# microcondsk.net
KiCad netlist of a schematic drawn in EAGLE
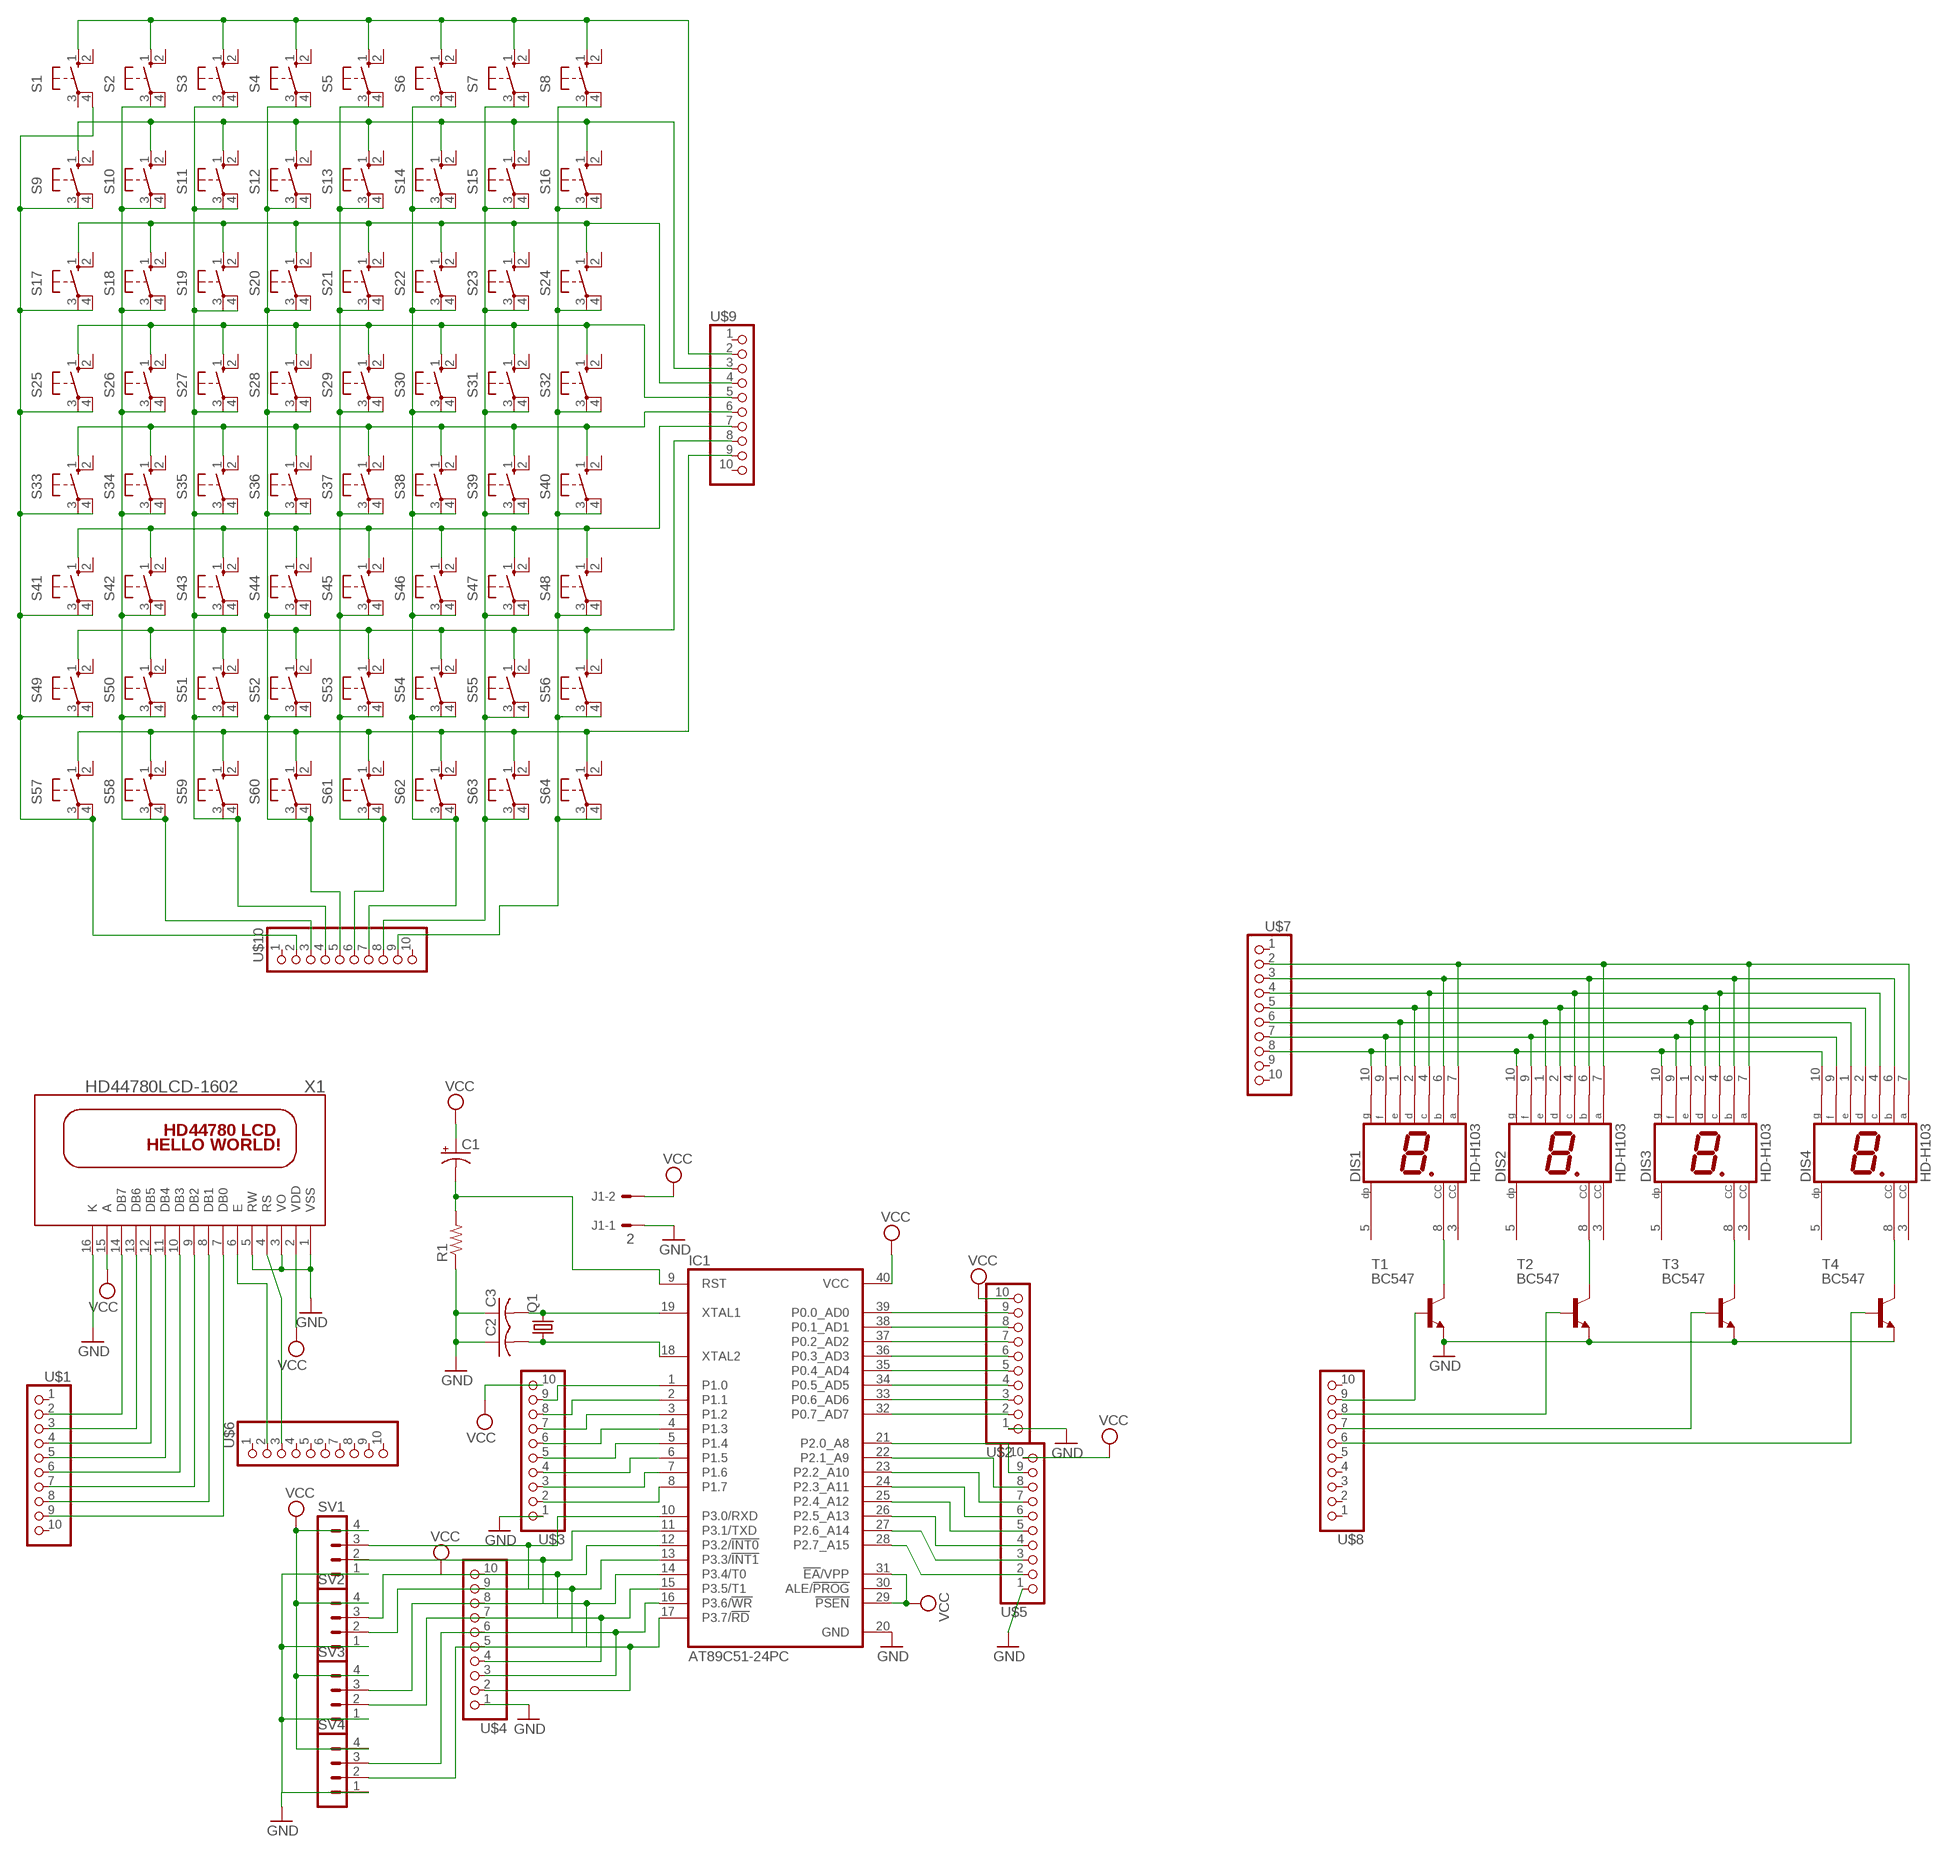
[diagram p0: schematic, sheet 1]

(export (version "E")
  (design (tool "Eeschema 10.0.6"))
  (components
    (comp (ref "C1")
      (value "CPOL-USE2-5")
      (footprint "eagle-import:E2-5")
      (libsource (lib "eagle-import") (part "CPOL-USE2-5"))
    )
    (comp (ref "C2")
      (value "C-US025-025X050")
      (footprint "eagle-import:C025-025X050")
      (libsource (lib "eagle-import") (part "C-US025-025X050"))
    )
    (comp (ref "C3")
      (value "C-US025-025X050")
      (footprint "eagle-import:C025-025X050")
      (libsource (lib "eagle-import") (part "C-US025-025X050"))
    )
    (comp (ref "DIS1")
      (value "HD-H103")
      (footprint "eagle-import:HDSP-M")
      (libsource (lib "eagle-import") (part "HD-H103"))
    )
    (comp (ref "DIS2")
      (value "HD-H103")
      (footprint "eagle-import:HDSP-M")
      (libsource (lib "eagle-import") (part "HD-H103"))
    )
    (comp (ref "DIS3")
      (value "HD-H103")
      (footprint "eagle-import:HDSP-M")
      (libsource (lib "eagle-import") (part "HD-H103"))
    )
    (comp (ref "DIS4")
      (value "HD-H103")
      (footprint "eagle-import:HDSP-M")
      (libsource (lib "eagle-import") (part "HD-H103"))
    )
    (comp (ref "IC1")
      (value "AT89C51-24PC")
      (footprint "eagle-import:DIL40")
      (libsource (lib "eagle-import") (part "AT89C51-PC24"))
    )
    (comp (ref "J1")
      (value "2")
      (footprint "eagle-import:6410-02")
      (libsource (lib "eagle-import") (part "22-?-0227-2021"))
    )
    (comp (ref "Q1")
      (value "CRYSTALHC49U-V")
      (footprint "eagle-import:HC49U-V")
      (libsource (lib "eagle-import") (part "CRYSTALHC49U-V"))
    )
    (comp (ref "R1")
      (value "R-US_0204/7")
      (footprint "eagle-import:0204_7")
      (libsource (lib "eagle-import") (part "R-US_0204/7"))
    )
    (comp (ref "S1")
      (value "10-XX")
      (footprint "eagle-import:B3F-10XX")
      (fields (field (name "MPN") "B3F-1000"))
      (libsource (lib "eagle-import") (part "10-XX"))
    )
    (comp (ref "S2")
      (value "10-XX")
      (footprint "eagle-import:B3F-10XX")
      (fields (field (name "MPN") "B3F-1000"))
      (libsource (lib "eagle-import") (part "10-XX"))
    )
    (comp (ref "S3")
      (value "10-XX")
      (footprint "eagle-import:B3F-10XX")
      (fields (field (name "MPN") "B3F-1000"))
      (libsource (lib "eagle-import") (part "10-XX"))
    )
    (comp (ref "S4")
      (value "10-XX")
      (footprint "eagle-import:B3F-10XX")
      (fields (field (name "MPN") "B3F-1000"))
      (libsource (lib "eagle-import") (part "10-XX"))
    )
    (comp (ref "S5")
      (value "10-XX")
      (footprint "eagle-import:B3F-10XX")
      (fields (field (name "MPN") "B3F-1000"))
      (libsource (lib "eagle-import") (part "10-XX"))
    )
    (comp (ref "S6")
      (value "10-XX")
      (footprint "eagle-import:B3F-10XX")
      (fields (field (name "MPN") "B3F-1000"))
      (libsource (lib "eagle-import") (part "10-XX"))
    )
    (comp (ref "S7")
      (value "10-XX")
      (footprint "eagle-import:B3F-10XX")
      (fields (field (name "MPN") "B3F-1000"))
      (libsource (lib "eagle-import") (part "10-XX"))
    )
    (comp (ref "S8")
      (value "10-XX")
      (footprint "eagle-import:B3F-10XX")
      (fields (field (name "MPN") "B3F-1000"))
      (libsource (lib "eagle-import") (part "10-XX"))
    )
    (comp (ref "S9")
      (value "10-XX")
      (footprint "eagle-import:B3F-10XX")
      (fields (field (name "MPN") "B3F-1000"))
      (libsource (lib "eagle-import") (part "10-XX"))
    )
    (comp (ref "S10")
      (value "10-XX")
      (footprint "eagle-import:B3F-10XX")
      (fields (field (name "MPN") "B3F-1000"))
      (libsource (lib "eagle-import") (part "10-XX"))
    )
    (comp (ref "S11")
      (value "10-XX")
      (footprint "eagle-import:B3F-10XX")
      (fields (field (name "MPN") "B3F-1000"))
      (libsource (lib "eagle-import") (part "10-XX"))
    )
    (comp (ref "S12")
      (value "10-XX")
      (footprint "eagle-import:B3F-10XX")
      (fields (field (name "MPN") "B3F-1000"))
      (libsource (lib "eagle-import") (part "10-XX"))
    )
    (comp (ref "S13")
      (value "10-XX")
      (footprint "eagle-import:B3F-10XX")
      (fields (field (name "MPN") "B3F-1000"))
      (libsource (lib "eagle-import") (part "10-XX"))
    )
    (comp (ref "S14")
      (value "10-XX")
      (footprint "eagle-import:B3F-10XX")
      (fields (field (name "MPN") "B3F-1000"))
      (libsource (lib "eagle-import") (part "10-XX"))
    )
    (comp (ref "S15")
      (value "10-XX")
      (footprint "eagle-import:B3F-10XX")
      (fields (field (name "MPN") "B3F-1000"))
      (libsource (lib "eagle-import") (part "10-XX"))
    )
    (comp (ref "S16")
      (value "10-XX")
      (footprint "eagle-import:B3F-10XX")
      (fields (field (name "MPN") "B3F-1000"))
      (libsource (lib "eagle-import") (part "10-XX"))
    )
    (comp (ref "S17")
      (value "10-XX")
      (footprint "eagle-import:B3F-10XX")
      (fields (field (name "MPN") "B3F-1000"))
      (libsource (lib "eagle-import") (part "10-XX"))
    )
    (comp (ref "S18")
      (value "10-XX")
      (footprint "eagle-import:B3F-10XX")
      (fields (field (name "MPN") "B3F-1000"))
      (libsource (lib "eagle-import") (part "10-XX"))
    )
    (comp (ref "S19")
      (value "10-XX")
      (footprint "eagle-import:B3F-10XX")
      (fields (field (name "MPN") "B3F-1000"))
      (libsource (lib "eagle-import") (part "10-XX"))
    )
    (comp (ref "S20")
      (value "10-XX")
      (footprint "eagle-import:B3F-10XX")
      (fields (field (name "MPN") "B3F-1000"))
      (libsource (lib "eagle-import") (part "10-XX"))
    )
    (comp (ref "S21")
      (value "10-XX")
      (footprint "eagle-import:B3F-10XX")
      (fields (field (name "MPN") "B3F-1000"))
      (libsource (lib "eagle-import") (part "10-XX"))
    )
    (comp (ref "S22")
      (value "10-XX")
      (footprint "eagle-import:B3F-10XX")
      (fields (field (name "MPN") "B3F-1000"))
      (libsource (lib "eagle-import") (part "10-XX"))
    )
    (comp (ref "S23")
      (value "10-XX")
      (footprint "eagle-import:B3F-10XX")
      (fields (field (name "MPN") "B3F-1000"))
      (libsource (lib "eagle-import") (part "10-XX"))
    )
    (comp (ref "S24")
      (value "10-XX")
      (footprint "eagle-import:B3F-10XX")
      (fields (field (name "MPN") "B3F-1000"))
      (libsource (lib "eagle-import") (part "10-XX"))
    )
    (comp (ref "S25")
      (value "10-XX")
      (footprint "eagle-import:B3F-10XX")
      (fields (field (name "MPN") "B3F-1000"))
      (libsource (lib "eagle-import") (part "10-XX"))
    )
    (comp (ref "S26")
      (value "10-XX")
      (footprint "eagle-import:B3F-10XX")
      (fields (field (name "MPN") "B3F-1000"))
      (libsource (lib "eagle-import") (part "10-XX"))
    )
    (comp (ref "S27")
      (value "10-XX")
      (footprint "eagle-import:B3F-10XX")
      (fields (field (name "MPN") "B3F-1000"))
      (libsource (lib "eagle-import") (part "10-XX"))
    )
    (comp (ref "S28")
      (value "10-XX")
      (footprint "eagle-import:B3F-10XX")
      (fields (field (name "MPN") "B3F-1000"))
      (libsource (lib "eagle-import") (part "10-XX"))
    )
    (comp (ref "S29")
      (value "10-XX")
      (footprint "eagle-import:B3F-10XX")
      (fields (field (name "MPN") "B3F-1000"))
      (libsource (lib "eagle-import") (part "10-XX"))
    )
    (comp (ref "S30")
      (value "10-XX")
      (footprint "eagle-import:B3F-10XX")
      (fields (field (name "MPN") "B3F-1000"))
      (libsource (lib "eagle-import") (part "10-XX"))
    )
    (comp (ref "S31")
      (value "10-XX")
      (footprint "eagle-import:B3F-10XX")
      (fields (field (name "MPN") "B3F-1000"))
      (libsource (lib "eagle-import") (part "10-XX"))
    )
    (comp (ref "S32")
      (value "10-XX")
      (footprint "eagle-import:B3F-10XX")
      (fields (field (name "MPN") "B3F-1000"))
      (libsource (lib "eagle-import") (part "10-XX"))
    )
    (comp (ref "S33")
      (value "10-XX")
      (footprint "eagle-import:B3F-10XX")
      (fields (field (name "MPN") "B3F-1000"))
      (libsource (lib "eagle-import") (part "10-XX"))
    )
    (comp (ref "S34")
      (value "10-XX")
      (footprint "eagle-import:B3F-10XX")
      (fields (field (name "MPN") "B3F-1000"))
      (libsource (lib "eagle-import") (part "10-XX"))
    )
    (comp (ref "S35")
      (value "10-XX")
      (footprint "eagle-import:B3F-10XX")
      (fields (field (name "MPN") "B3F-1000"))
      (libsource (lib "eagle-import") (part "10-XX"))
    )
    (comp (ref "S36")
      (value "10-XX")
      (footprint "eagle-import:B3F-10XX")
      (fields (field (name "MPN") "B3F-1000"))
      (libsource (lib "eagle-import") (part "10-XX"))
    )
    (comp (ref "S37")
      (value "10-XX")
      (footprint "eagle-import:B3F-10XX")
      (fields (field (name "MPN") "B3F-1000"))
      (libsource (lib "eagle-import") (part "10-XX"))
    )
    (comp (ref "S38")
      (value "10-XX")
      (footprint "eagle-import:B3F-10XX")
      (fields (field (name "MPN") "B3F-1000"))
      (libsource (lib "eagle-import") (part "10-XX"))
    )
    (comp (ref "S39")
      (value "10-XX")
      (footprint "eagle-import:B3F-10XX")
      (fields (field (name "MPN") "B3F-1000"))
      (libsource (lib "eagle-import") (part "10-XX"))
    )
    (comp (ref "S40")
      (value "10-XX")
      (footprint "eagle-import:B3F-10XX")
      (fields (field (name "MPN") "B3F-1000"))
      (libsource (lib "eagle-import") (part "10-XX"))
    )
    (comp (ref "S41")
      (value "10-XX")
      (footprint "eagle-import:B3F-10XX")
      (fields (field (name "MPN") "B3F-1000"))
      (libsource (lib "eagle-import") (part "10-XX"))
    )
    (comp (ref "S42")
      (value "10-XX")
      (footprint "eagle-import:B3F-10XX")
      (fields (field (name "MPN") "B3F-1000"))
      (libsource (lib "eagle-import") (part "10-XX"))
    )
    (comp (ref "S43")
      (value "10-XX")
      (footprint "eagle-import:B3F-10XX")
      (fields (field (name "MPN") "B3F-1000"))
      (libsource (lib "eagle-import") (part "10-XX"))
    )
    (comp (ref "S44")
      (value "10-XX")
      (footprint "eagle-import:B3F-10XX")
      (fields (field (name "MPN") "B3F-1000"))
      (libsource (lib "eagle-import") (part "10-XX"))
    )
    (comp (ref "S45")
      (value "10-XX")
      (footprint "eagle-import:B3F-10XX")
      (fields (field (name "MPN") "B3F-1000"))
      (libsource (lib "eagle-import") (part "10-XX"))
    )
    (comp (ref "S46")
      (value "10-XX")
      (footprint "eagle-import:B3F-10XX")
      (fields (field (name "MPN") "B3F-1000"))
      (libsource (lib "eagle-import") (part "10-XX"))
    )
    (comp (ref "S47")
      (value "10-XX")
      (footprint "eagle-import:B3F-10XX")
      (fields (field (name "MPN") "B3F-1000"))
      (libsource (lib "eagle-import") (part "10-XX"))
    )
    (comp (ref "S48")
      (value "10-XX")
      (footprint "eagle-import:B3F-10XX")
      (fields (field (name "MPN") "B3F-1000"))
      (libsource (lib "eagle-import") (part "10-XX"))
    )
    (comp (ref "S49")
      (value "10-XX")
      (footprint "eagle-import:B3F-10XX")
      (fields (field (name "MPN") "B3F-1000"))
      (libsource (lib "eagle-import") (part "10-XX"))
    )
    (comp (ref "S50")
      (value "10-XX")
      (footprint "eagle-import:B3F-10XX")
      (fields (field (name "MPN") "B3F-1000"))
      (libsource (lib "eagle-import") (part "10-XX"))
    )
    (comp (ref "S51")
      (value "10-XX")
      (footprint "eagle-import:B3F-10XX")
      (fields (field (name "MPN") "B3F-1000"))
      (libsource (lib "eagle-import") (part "10-XX"))
    )
    (comp (ref "S52")
      (value "10-XX")
      (footprint "eagle-import:B3F-10XX")
      (fields (field (name "MPN") "B3F-1000"))
      (libsource (lib "eagle-import") (part "10-XX"))
    )
    (comp (ref "S53")
      (value "10-XX")
      (footprint "eagle-import:B3F-10XX")
      (fields (field (name "MPN") "B3F-1000"))
      (libsource (lib "eagle-import") (part "10-XX"))
    )
    (comp (ref "S54")
      (value "10-XX")
      (footprint "eagle-import:B3F-10XX")
      (fields (field (name "MPN") "B3F-1000"))
      (libsource (lib "eagle-import") (part "10-XX"))
    )
    (comp (ref "S55")
      (value "10-XX")
      (footprint "eagle-import:B3F-10XX")
      (fields (field (name "MPN") "B3F-1000"))
      (libsource (lib "eagle-import") (part "10-XX"))
    )
    (comp (ref "S56")
      (value "10-XX")
      (footprint "eagle-import:B3F-10XX")
      (fields (field (name "MPN") "B3F-1000"))
      (libsource (lib "eagle-import") (part "10-XX"))
    )
    (comp (ref "S57")
      (value "10-XX")
      (footprint "eagle-import:B3F-10XX")
      (fields (field (name "MPN") "B3F-1000"))
      (libsource (lib "eagle-import") (part "10-XX"))
    )
    (comp (ref "S58")
      (value "10-XX")
      (footprint "eagle-import:B3F-10XX")
      (fields (field (name "MPN") "B3F-1000"))
      (libsource (lib "eagle-import") (part "10-XX"))
    )
    (comp (ref "S59")
      (value "10-XX")
      (footprint "eagle-import:B3F-10XX")
      (fields (field (name "MPN") "B3F-1000"))
      (libsource (lib "eagle-import") (part "10-XX"))
    )
    (comp (ref "S60")
      (value "10-XX")
      (footprint "eagle-import:B3F-10XX")
      (fields (field (name "MPN") "B3F-1000"))
      (libsource (lib "eagle-import") (part "10-XX"))
    )
    (comp (ref "S61")
      (value "10-XX")
      (footprint "eagle-import:B3F-10XX")
      (fields (field (name "MPN") "B3F-1000"))
      (libsource (lib "eagle-import") (part "10-XX"))
    )
    (comp (ref "S62")
      (value "10-XX")
      (footprint "eagle-import:B3F-10XX")
      (fields (field (name "MPN") "B3F-1000"))
      (libsource (lib "eagle-import") (part "10-XX"))
    )
    (comp (ref "S63")
      (value "10-XX")
      (footprint "eagle-import:B3F-10XX")
      (fields (field (name "MPN") "B3F-1000"))
      (libsource (lib "eagle-import") (part "10-XX"))
    )
    (comp (ref "S64")
      (value "10-XX")
      (footprint "eagle-import:B3F-10XX")
      (fields (field (name "MPN") "B3F-1000"))
      (libsource (lib "eagle-import") (part "10-XX"))
    )
    (comp (ref "SV1")
      (value "MA04-1")
      (footprint "eagle-import:MA04-1")
      (libsource (lib "eagle-import") (part "MA04-1"))
    )
    (comp (ref "SV2")
      (value "MA04-1")
      (footprint "eagle-import:MA04-1")
      (libsource (lib "eagle-import") (part "MA04-1"))
    )
    (comp (ref "SV3")
      (value "MA04-1")
      (footprint "eagle-import:MA04-1")
      (libsource (lib "eagle-import") (part "MA04-1"))
    )
    (comp (ref "SV4")
      (value "MA04-1")
      (footprint "eagle-import:MA04-1")
      (libsource (lib "eagle-import") (part "MA04-1"))
    )
    (comp (ref "T1")
      (value "BC547")
      (footprint "eagle-import:TO92")
      (libsource (lib "eagle-import") (part "BC547"))
    )
    (comp (ref "T2")
      (value "BC547")
      (footprint "eagle-import:TO92")
      (libsource (lib "eagle-import") (part "BC547"))
    )
    (comp (ref "T3")
      (value "BC547")
      (footprint "eagle-import:TO92")
      (libsource (lib "eagle-import") (part "BC547"))
    )
    (comp (ref "T4")
      (value "BC547")
      (footprint "eagle-import:TO92")
      (libsource (lib "eagle-import") (part "BC547"))
    )
    (comp (ref "U$1")
      (value "PINHD-1X10")
      (footprint "eagle-import:1X10-BIG")
      (libsource (lib "eagle-import") (part "PINHD-1X10"))
    )
    (comp (ref "U$2")
      (value "PINHD-1X10")
      (footprint "eagle-import:1X10-BIG")
      (libsource (lib "eagle-import") (part "PINHD-1X10"))
    )
    (comp (ref "U$3")
      (value "PINHD-1X10")
      (footprint "eagle-import:1X10-BIG")
      (libsource (lib "eagle-import") (part "PINHD-1X10"))
    )
    (comp (ref "U$4")
      (value "PINHD-1X10")
      (footprint "eagle-import:1X10-BIG")
      (libsource (lib "eagle-import") (part "PINHD-1X10"))
    )
    (comp (ref "U$5")
      (value "PINHD-1X10")
      (footprint "eagle-import:1X10-BIG")
      (libsource (lib "eagle-import") (part "PINHD-1X10"))
    )
    (comp (ref "U$6")
      (value "PINHD-1X10")
      (footprint "eagle-import:1X10-BIG")
      (libsource (lib "eagle-import") (part "PINHD-1X10"))
    )
    (comp (ref "U$7")
      (value "PINHD-1X10")
      (footprint "eagle-import:1X10-BIG")
      (libsource (lib "eagle-import") (part "PINHD-1X10"))
    )
    (comp (ref "U$8")
      (value "PINHD-1X10")
      (footprint "eagle-import:1X10-BIG")
      (libsource (lib "eagle-import") (part "PINHD-1X10"))
    )
    (comp (ref "U$9")
      (value "PINHD-1X10")
      (footprint "eagle-import:1X10-BIG")
      (libsource (lib "eagle-import") (part "PINHD-1X10"))
    )
    (comp (ref "U$10")
      (value "PINHD-1X10")
      (footprint "eagle-import:1X10-BIG")
      (libsource (lib "eagle-import") (part "PINHD-1X10"))
    )
    (comp (ref "X1")
      (value "HD44780LCD-1602")
      (footprint "eagle-import:LCD1602")
      (libsource (lib "eagle-import") (part "HD44780LCD-1602"))
    )
  )
  (nets
    (net (code "1") (name "GND") (class "Default")
      (node (ref "C2") (pin "1") (pinfunction "1_1") (pintype "passive"))
      (node (ref "C3") (pin "1") (pinfunction "1_1") (pintype "passive"))
      (node (ref "IC1") (pin "20") (pinfunction "GND_20") (pintype "power_in"))
      (node (ref "J1") (pin "1") (pinfunction "S_1") (pintype "passive"))
      (node (ref "R1") (pin "1") (pinfunction "1_1") (pintype "passive"))
      (node (ref "SV1") (pin "1") (pinfunction "1_1") (pintype "passive"))
      (node (ref "SV2") (pin "1") (pinfunction "1_1") (pintype "passive"))
      (node (ref "SV3") (pin "1") (pinfunction "1_1") (pintype "passive"))
      (node (ref "SV4") (pin "1") (pinfunction "1_1") (pintype "passive"))
      (node (ref "T1") (pin "1") (pinfunction "E_1") (pintype "passive"))
      (node (ref "T2") (pin "1") (pinfunction "E_1") (pintype "passive"))
      (node (ref "T3") (pin "1") (pinfunction "E_1") (pintype "passive"))
      (node (ref "T4") (pin "1") (pinfunction "E_1") (pintype "passive"))
      (node (ref "U$2") (pin "1") (pinfunction "1_1") (pintype "passive"))
      (node (ref "U$3") (pin "1") (pinfunction "1_1") (pintype "passive"))
      (node (ref "U$4") (pin "1") (pinfunction "1_1") (pintype "passive"))
      (node (ref "U$5") (pin "1") (pinfunction "1_1") (pintype "passive"))
      (node (ref "X1") (pin "1") (pinfunction "VSS_1") (pintype "power_in"))
      (node (ref "X1") (pin "16") (pinfunction "K_16") (pintype "input"))
      (node (ref "X1") (pin "3") (pinfunction "VO_3") (pintype "input"))
      (node (ref "X1") (pin "5") (pinfunction "RW_5") (pintype "input"))
    )
    (net (code "2") (name "Net-(DIS1-A)") (class "Default")
      (node (ref "DIS1") (pin "7") (pinfunction "A_7") (pintype "passive"))
      (node (ref "DIS2") (pin "7") (pinfunction "A_7") (pintype "passive"))
      (node (ref "DIS3") (pin "7") (pinfunction "A_7") (pintype "passive"))
      (node (ref "U$7") (pin "2") (pinfunction "2_2") (pintype "passive"))
    )
    (net (code "3") (name "Net-(DIS1-B)") (class "Default")
      (node (ref "DIS1") (pin "6") (pinfunction "B_6") (pintype "passive"))
      (node (ref "DIS2") (pin "6") (pinfunction "B_6") (pintype "passive"))
      (node (ref "DIS3") (pin "6") (pinfunction "B_6") (pintype "passive"))
      (node (ref "DIS4") (pin "6") (pinfunction "B_6") (pintype "passive"))
      (node (ref "U$7") (pin "3") (pinfunction "3_3") (pintype "passive"))
    )
    (net (code "4") (name "Net-(DIS1-C)") (class "Default")
      (node (ref "DIS1") (pin "4") (pinfunction "C_4") (pintype "passive"))
      (node (ref "DIS2") (pin "4") (pinfunction "C_4") (pintype "passive"))
      (node (ref "DIS3") (pin "4") (pinfunction "C_4") (pintype "passive"))
      (node (ref "DIS4") (pin "4") (pinfunction "C_4") (pintype "passive"))
      (node (ref "U$7") (pin "4") (pinfunction "4_4") (pintype "passive"))
    )
    (net (code "5") (name "Net-(DIS1-D)") (class "Default")
      (node (ref "DIS1") (pin "2") (pinfunction "D_2") (pintype "passive"))
      (node (ref "DIS2") (pin "2") (pinfunction "D_2") (pintype "passive"))
      (node (ref "DIS3") (pin "2") (pinfunction "D_2") (pintype "passive"))
      (node (ref "DIS4") (pin "2") (pinfunction "D_2") (pintype "passive"))
      (node (ref "U$7") (pin "5") (pinfunction "5_5") (pintype "passive"))
    )
    (net (code "6") (name "Net-(DIS1-E)") (class "Default")
      (node (ref "DIS1") (pin "1") (pinfunction "E_1") (pintype "passive"))
      (node (ref "DIS2") (pin "1") (pinfunction "E_1") (pintype "passive"))
      (node (ref "DIS3") (pin "1") (pinfunction "E_1") (pintype "passive"))
      (node (ref "DIS4") (pin "1") (pinfunction "E_1") (pintype "passive"))
      (node (ref "U$7") (pin "6") (pinfunction "6_6") (pintype "passive"))
    )
    (net (code "7") (name "Net-(DIS1-F)") (class "Default")
      (node (ref "DIS1") (pin "9") (pinfunction "F_9") (pintype "passive"))
      (node (ref "DIS2") (pin "9") (pinfunction "F_9") (pintype "passive"))
      (node (ref "DIS3") (pin "9") (pinfunction "F_9") (pintype "passive"))
      (node (ref "DIS4") (pin "9") (pinfunction "F_9") (pintype "passive"))
      (node (ref "U$7") (pin "7") (pinfunction "7_7") (pintype "passive"))
    )
    (net (code "8") (name "Net-(DIS1-G)") (class "Default")
      (node (ref "DIS1") (pin "10") (pinfunction "G_10") (pintype "passive"))
      (node (ref "DIS2") (pin "10") (pinfunction "G_10") (pintype "passive"))
      (node (ref "DIS3") (pin "10") (pinfunction "G_10") (pintype "passive"))
      (node (ref "DIS4") (pin "10") (pinfunction "G_10") (pintype "passive"))
      (node (ref "U$7") (pin "8") (pinfunction "8_8") (pintype "passive"))
    )
    (net (code "9") (name "Net-(IC1-P0.0_AD0)") (class "Default")
      (node (ref "IC1") (pin "39") (pinfunction "P0.0_AD0_39") (pintype "bidirectional"))
      (node (ref "U$2") (pin "9") (pinfunction "9_9") (pintype "passive"))
    )
    (net (code "10") (name "Net-(IC1-P0.1_AD1)") (class "Default")
      (node (ref "IC1") (pin "38") (pinfunction "P0.1_AD1_38") (pintype "bidirectional"))
      (node (ref "U$2") (pin "8") (pinfunction "8_8") (pintype "passive"))
    )
    (net (code "11") (name "Net-(IC1-P0.2_AD2)") (class "Default")
      (node (ref "IC1") (pin "37") (pinfunction "P0.2_AD2_37") (pintype "bidirectional"))
      (node (ref "U$2") (pin "7") (pinfunction "7_7") (pintype "passive"))
    )
    (net (code "12") (name "Net-(IC1-P0.3_AD3)") (class "Default")
      (node (ref "IC1") (pin "36") (pinfunction "P0.3_AD3_36") (pintype "bidirectional"))
      (node (ref "U$2") (pin "6") (pinfunction "6_6") (pintype "passive"))
    )
    (net (code "13") (name "Net-(IC1-P0.4_AD4)") (class "Default")
      (node (ref "IC1") (pin "35") (pinfunction "P0.4_AD4_35") (pintype "bidirectional"))
      (node (ref "U$2") (pin "5") (pinfunction "5_5") (pintype "passive"))
    )
    (net (code "14") (name "Net-(IC1-P0.5_AD5)") (class "Default")
      (node (ref "IC1") (pin "34") (pinfunction "P0.5_AD5_34") (pintype "bidirectional"))
      (node (ref "U$2") (pin "4") (pinfunction "4_4") (pintype "passive"))
    )
    (net (code "15") (name "Net-(IC1-P0.6_AD6)") (class "Default")
      (node (ref "IC1") (pin "33") (pinfunction "P0.6_AD6_33") (pintype "bidirectional"))
      (node (ref "U$2") (pin "3") (pinfunction "3_3") (pintype "passive"))
    )
    (net (code "16") (name "Net-(IC1-P0.7_AD7)") (class "Default")
      (node (ref "IC1") (pin "32") (pinfunction "P0.7_AD7_32") (pintype "bidirectional"))
      (node (ref "U$2") (pin "2") (pinfunction "2_2") (pintype "passive"))
    )
    (net (code "17") (name "Net-(IC1-P1.0)") (class "Default")
      (node (ref "IC1") (pin "1") (pinfunction "P1.0_1") (pintype "bidirectional"))
      (node (ref "U$3") (pin "9") (pinfunction "9_9") (pintype "passive"))
    )
    (net (code "18") (name "Net-(IC1-P1.1)") (class "Default")
      (node (ref "IC1") (pin "2") (pinfunction "P1.1_2") (pintype "bidirectional"))
      (node (ref "U$3") (pin "8") (pinfunction "8_8") (pintype "passive"))
    )
    (net (code "19") (name "Net-(IC1-P1.2)") (class "Default")
      (node (ref "IC1") (pin "3") (pinfunction "P1.2_3") (pintype "bidirectional"))
      (node (ref "U$3") (pin "7") (pinfunction "7_7") (pintype "passive"))
    )
    (net (code "20") (name "Net-(IC1-P1.3)") (class "Default")
      (node (ref "IC1") (pin "4") (pinfunction "P1.3_4") (pintype "bidirectional"))
      (node (ref "U$3") (pin "6") (pinfunction "6_6") (pintype "passive"))
    )
    (net (code "21") (name "Net-(IC1-P1.4)") (class "Default")
      (node (ref "IC1") (pin "5") (pinfunction "P1.4_5") (pintype "bidirectional"))
      (node (ref "U$3") (pin "5") (pinfunction "5_5") (pintype "passive"))
    )
    (net (code "22") (name "Net-(IC1-P1.5)") (class "Default")
      (node (ref "IC1") (pin "6") (pinfunction "P1.5_6") (pintype "bidirectional"))
      (node (ref "U$3") (pin "4") (pinfunction "4_4") (pintype "passive"))
    )
    (net (code "23") (name "Net-(IC1-P1.6)") (class "Default")
      (node (ref "IC1") (pin "7") (pinfunction "P1.6_7") (pintype "bidirectional"))
      (node (ref "U$3") (pin "3") (pinfunction "3_3") (pintype "passive"))
    )
    (net (code "24") (name "Net-(IC1-P1.7)") (class "Default")
      (node (ref "IC1") (pin "8") (pinfunction "P1.7_8") (pintype "bidirectional"))
      (node (ref "U$3") (pin "2") (pinfunction "2_2") (pintype "passive"))
    )
    (net (code "25") (name "Net-(IC1-P2.0_A8)") (class "Default")
      (node (ref "IC1") (pin "21") (pinfunction "P2.0_A8_21") (pintype "bidirectional"))
      (node (ref "U$5") (pin "9") (pinfunction "9_9") (pintype "passive"))
    )
    (net (code "26") (name "Net-(IC1-P2.1_A9)") (class "Default")
      (node (ref "IC1") (pin "22") (pinfunction "P2.1_A9_22") (pintype "bidirectional"))
      (node (ref "U$5") (pin "8") (pinfunction "8_8") (pintype "passive"))
    )
    (net (code "27") (name "Net-(IC1-P2.2_A10)") (class "Default")
      (node (ref "IC1") (pin "23") (pinfunction "P2.2_A10_23") (pintype "bidirectional"))
      (node (ref "U$5") (pin "7") (pinfunction "7_7") (pintype "passive"))
    )
    (net (code "28") (name "Net-(IC1-P2.3_A11)") (class "Default")
      (node (ref "IC1") (pin "24") (pinfunction "P2.3_A11_24") (pintype "bidirectional"))
      (node (ref "U$5") (pin "6") (pinfunction "6_6") (pintype "passive"))
    )
    (net (code "29") (name "Net-(IC1-P2.4_A12)") (class "Default")
      (node (ref "IC1") (pin "25") (pinfunction "P2.4_A12_25") (pintype "bidirectional"))
      (node (ref "U$5") (pin "5") (pinfunction "5_5") (pintype "passive"))
    )
    (net (code "30") (name "Net-(IC1-P2.5_A13)") (class "Default")
      (node (ref "IC1") (pin "26") (pinfunction "P2.5_A13_26") (pintype "bidirectional"))
      (node (ref "U$5") (pin "4") (pinfunction "4_4") (pintype "passive"))
    )
    (net (code "31") (name "Net-(IC1-P2.6_A14)") (class "Default")
      (node (ref "IC1") (pin "27") (pinfunction "P2.6_A14_27") (pintype "bidirectional"))
      (node (ref "U$5") (pin "3") (pinfunction "3_3") (pintype "passive"))
    )
    (net (code "32") (name "Net-(IC1-P2.7_A15)") (class "Default")
      (node (ref "IC1") (pin "28") (pinfunction "P2.7_A15_28") (pintype "bidirectional"))
      (node (ref "U$5") (pin "2") (pinfunction "2_2") (pintype "passive"))
    )
    (net (code "33") (name "Net-(IC1-P3.0{slash}RXD)") (class "Default")
      (node (ref "IC1") (pin "10") (pinfunction "P3.0/RXD_10") (pintype "bidirectional"))
      (node (ref "SV1") (pin "3") (pinfunction "3_3") (pintype "passive"))
      (node (ref "U$4") (pin "9") (pinfunction "9_9") (pintype "passive"))
    )
    (net (code "34") (name "Net-(IC1-P3.1{slash}TXD)") (class "Default")
      (node (ref "IC1") (pin "11") (pinfunction "P3.1/TXD_11") (pintype "bidirectional"))
      (node (ref "SV1") (pin "2") (pinfunction "2_2") (pintype "passive"))
      (node (ref "U$4") (pin "8") (pinfunction "8_8") (pintype "passive"))
    )
    (net (code "35") (name "Net-(IC1-P3.2{slash}~{INT0})") (class "Default")
      (node (ref "IC1") (pin "12") (pinfunction "P3.2/~{INT0}_12") (pintype "bidirectional"))
      (node (ref "SV2") (pin "3") (pinfunction "3_3") (pintype "passive"))
      (node (ref "U$4") (pin "7") (pinfunction "7_7") (pintype "passive"))
    )
    (net (code "36") (name "Net-(IC1-P3.3{slash}~{INT1})") (class "Default")
      (node (ref "IC1") (pin "13") (pinfunction "P3.3/~{INT1}_13") (pintype "bidirectional"))
      (node (ref "SV2") (pin "2") (pinfunction "2_2") (pintype "passive"))
      (node (ref "U$4") (pin "6") (pinfunction "6_6") (pintype "passive"))
    )
    (net (code "37") (name "Net-(IC1-P3.4{slash}T0)") (class "Default")
      (node (ref "IC1") (pin "14") (pinfunction "P3.4/T0_14") (pintype "bidirectional"))
      (node (ref "SV3") (pin "3") (pinfunction "3_3") (pintype "passive"))
      (node (ref "U$4") (pin "5") (pinfunction "5_5") (pintype "passive"))
    )
    (net (code "38") (name "Net-(IC1-P3.5{slash}T1)") (class "Default")
      (node (ref "IC1") (pin "15") (pinfunction "P3.5/T1_15") (pintype "bidirectional"))
      (node (ref "SV3") (pin "2") (pinfunction "2_2") (pintype "passive"))
      (node (ref "U$4") (pin "4") (pinfunction "4_4") (pintype "passive"))
    )
    (net (code "39") (name "Net-(IC1-P3.6{slash}~{WR})") (class "Default")
      (node (ref "IC1") (pin "16") (pinfunction "P3.6/~{WR}_16") (pintype "bidirectional"))
      (node (ref "SV4") (pin "3") (pinfunction "3_3") (pintype "passive"))
      (node (ref "U$4") (pin "3") (pinfunction "3_3") (pintype "passive"))
    )
    (net (code "40") (name "Net-(IC1-P3.7{slash}~{RD})") (class "Default")
      (node (ref "IC1") (pin "17") (pinfunction "P3.7/~{RD}_17") (pintype "bidirectional"))
      (node (ref "SV4") (pin "2") (pinfunction "2_2") (pintype "passive"))
      (node (ref "U$4") (pin "2") (pinfunction "2_2") (pintype "passive"))
    )
    (net (code "41") (name "Net-(IC1-RST)") (class "Default")
      (node (ref "C1") (pin "-") (pinfunction "-_-") (pintype "passive"))
      (node (ref "IC1") (pin "9") (pinfunction "RST_9") (pintype "input"))
      (node (ref "R1") (pin "2") (pinfunction "2_2") (pintype "passive"))
    )
    (net (code "42") (name "Net-(IC1-XTAL1)") (class "Default")
      (node (ref "C3") (pin "2") (pinfunction "2_2") (pintype "passive"))
      (node (ref "IC1") (pin "19") (pinfunction "XTAL1_19") (pintype "input"))
      (node (ref "Q1") (pin "2") (pinfunction "2_2") (pintype "passive"))
    )
    (net (code "43") (name "Net-(IC1-XTAL2)") (class "Default")
      (node (ref "C2") (pin "2") (pinfunction "2_2") (pintype "passive"))
      (node (ref "IC1") (pin "18") (pinfunction "XTAL2_18") (pintype "input"))
      (node (ref "Q1") (pin "1") (pinfunction "1_1") (pintype "passive"))
    )
    (net (code "44") (name "Net-(S1-P1)") (class "Default")
      (node (ref "S1") (pin "4") (pinfunction "P1_4") (pintype "passive"))
      (node (ref "S17") (pin "4") (pinfunction "P1_4") (pintype "passive"))
      (node (ref "S25") (pin "4") (pinfunction "P1_4") (pintype "passive"))
      (node (ref "S33") (pin "4") (pinfunction "P1_4") (pintype "passive"))
      (node (ref "S41") (pin "4") (pinfunction "P1_4") (pintype "passive"))
      (node (ref "S49") (pin "4") (pinfunction "P1_4") (pintype "passive"))
      (node (ref "S57") (pin "4") (pinfunction "P1_4") (pintype "passive"))
      (node (ref "S9") (pin "4") (pinfunction "P1_4") (pintype "passive"))
      (node (ref "U$10") (pin "2") (pinfunction "2_2") (pintype "passive"))
    )
    (net (code "45") (name "Net-(S1-S)") (class "Default")
      (node (ref "S1") (pin "1") (pinfunction "S_1") (pintype "passive"))
      (node (ref "S2") (pin "1") (pinfunction "S_1") (pintype "passive"))
      (node (ref "S3") (pin "1") (pinfunction "S_1") (pintype "passive"))
      (node (ref "S4") (pin "1") (pinfunction "S_1") (pintype "passive"))
      (node (ref "S5") (pin "1") (pinfunction "S_1") (pintype "passive"))
      (node (ref "S6") (pin "1") (pinfunction "S_1") (pintype "passive"))
      (node (ref "S7") (pin "1") (pinfunction "S_1") (pintype "passive"))
      (node (ref "S8") (pin "1") (pinfunction "S_1") (pintype "passive"))
      (node (ref "U$9") (pin "2") (pinfunction "2_2") (pintype "passive"))
    )
    (net (code "46") (name "Net-(S10-P1)") (class "Default")
      (node (ref "S10") (pin "4") (pinfunction "P1_4") (pintype "passive"))
      (node (ref "S18") (pin "4") (pinfunction "P1_4") (pintype "passive"))
      (node (ref "S2") (pin "4") (pinfunction "P1_4") (pintype "passive"))
      (node (ref "S26") (pin "4") (pinfunction "P1_4") (pintype "passive"))
      (node (ref "S34") (pin "4") (pinfunction "P1_4") (pintype "passive"))
      (node (ref "S42") (pin "4") (pinfunction "P1_4") (pintype "passive"))
      (node (ref "S50") (pin "4") (pinfunction "P1_4") (pintype "passive"))
      (node (ref "S58") (pin "4") (pinfunction "P1_4") (pintype "passive"))
      (node (ref "U$10") (pin "3") (pinfunction "3_3") (pintype "passive"))
    )
    (net (code "47") (name "Net-(S10-S)") (class "Default")
      (node (ref "S10") (pin "1") (pinfunction "S_1") (pintype "passive"))
      (node (ref "S11") (pin "1") (pinfunction "S_1") (pintype "passive"))
      (node (ref "S12") (pin "1") (pinfunction "S_1") (pintype "passive"))
      (node (ref "S13") (pin "1") (pinfunction "S_1") (pintype "passive"))
      (node (ref "S14") (pin "1") (pinfunction "S_1") (pintype "passive"))
      (node (ref "S15") (pin "1") (pinfunction "S_1") (pintype "passive"))
      (node (ref "S16") (pin "1") (pinfunction "S_1") (pintype "passive"))
      (node (ref "S9") (pin "1") (pinfunction "S_1") (pintype "passive"))
      (node (ref "U$9") (pin "3") (pinfunction "3_3") (pintype "passive"))
    )
    (net (code "48") (name "Net-(S11-P1)") (class "Default")
      (node (ref "S11") (pin "4") (pinfunction "P1_4") (pintype "passive"))
      (node (ref "S19") (pin "4") (pinfunction "P1_4") (pintype "passive"))
      (node (ref "S27") (pin "4") (pinfunction "P1_4") (pintype "passive"))
      (node (ref "S3") (pin "4") (pinfunction "P1_4") (pintype "passive"))
      (node (ref "S35") (pin "4") (pinfunction "P1_4") (pintype "passive"))
      (node (ref "S43") (pin "4") (pinfunction "P1_4") (pintype "passive"))
      (node (ref "S51") (pin "4") (pinfunction "P1_4") (pintype "passive"))
      (node (ref "S59") (pin "4") (pinfunction "P1_4") (pintype "passive"))
      (node (ref "U$10") (pin "4") (pinfunction "4_4") (pintype "passive"))
    )
    (net (code "49") (name "Net-(S12-P1)") (class "Default")
      (node (ref "S12") (pin "4") (pinfunction "P1_4") (pintype "passive"))
      (node (ref "S20") (pin "4") (pinfunction "P1_4") (pintype "passive"))
      (node (ref "S28") (pin "4") (pinfunction "P1_4") (pintype "passive"))
      (node (ref "S36") (pin "4") (pinfunction "P1_4") (pintype "passive"))
      (node (ref "S4") (pin "4") (pinfunction "P1_4") (pintype "passive"))
      (node (ref "S44") (pin "4") (pinfunction "P1_4") (pintype "passive"))
      (node (ref "S52") (pin "4") (pinfunction "P1_4") (pintype "passive"))
      (node (ref "S60") (pin "4") (pinfunction "P1_4") (pintype "passive"))
      (node (ref "U$10") (pin "5") (pinfunction "5_5") (pintype "passive"))
    )
    (net (code "50") (name "Net-(S13-P1)") (class "Default")
      (node (ref "S13") (pin "4") (pinfunction "P1_4") (pintype "passive"))
      (node (ref "S21") (pin "4") (pinfunction "P1_4") (pintype "passive"))
      (node (ref "S29") (pin "4") (pinfunction "P1_4") (pintype "passive"))
      (node (ref "S37") (pin "4") (pinfunction "P1_4") (pintype "passive"))
      (node (ref "S45") (pin "4") (pinfunction "P1_4") (pintype "passive"))
      (node (ref "S5") (pin "4") (pinfunction "P1_4") (pintype "passive"))
      (node (ref "S53") (pin "4") (pinfunction "P1_4") (pintype "passive"))
      (node (ref "S61") (pin "4") (pinfunction "P1_4") (pintype "passive"))
      (node (ref "U$10") (pin "6") (pinfunction "6_6") (pintype "passive"))
    )
    (net (code "51") (name "Net-(S14-P1)") (class "Default")
      (node (ref "S14") (pin "4") (pinfunction "P1_4") (pintype "passive"))
      (node (ref "S22") (pin "4") (pinfunction "P1_4") (pintype "passive"))
      (node (ref "S30") (pin "4") (pinfunction "P1_4") (pintype "passive"))
      (node (ref "S38") (pin "4") (pinfunction "P1_4") (pintype "passive"))
      (node (ref "S46") (pin "4") (pinfunction "P1_4") (pintype "passive"))
      (node (ref "S54") (pin "4") (pinfunction "P1_4") (pintype "passive"))
      (node (ref "S6") (pin "4") (pinfunction "P1_4") (pintype "passive"))
      (node (ref "S62") (pin "4") (pinfunction "P1_4") (pintype "passive"))
      (node (ref "U$10") (pin "7") (pinfunction "7_7") (pintype "passive"))
    )
    (net (code "52") (name "Net-(S15-P1)") (class "Default")
      (node (ref "S15") (pin "4") (pinfunction "P1_4") (pintype "passive"))
      (node (ref "S23") (pin "4") (pinfunction "P1_4") (pintype "passive"))
      (node (ref "S31") (pin "4") (pinfunction "P1_4") (pintype "passive"))
      (node (ref "S39") (pin "4") (pinfunction "P1_4") (pintype "passive"))
      (node (ref "S47") (pin "4") (pinfunction "P1_4") (pintype "passive"))
      (node (ref "S55") (pin "4") (pinfunction "P1_4") (pintype "passive"))
      (node (ref "S63") (pin "4") (pinfunction "P1_4") (pintype "passive"))
      (node (ref "S7") (pin "4") (pinfunction "P1_4") (pintype "passive"))
      (node (ref "U$10") (pin "8") (pinfunction "8_8") (pintype "passive"))
    )
    (net (code "53") (name "Net-(S16-P1)") (class "Default")
      (node (ref "S16") (pin "4") (pinfunction "P1_4") (pintype "passive"))
      (node (ref "S24") (pin "4") (pinfunction "P1_4") (pintype "passive"))
      (node (ref "S32") (pin "4") (pinfunction "P1_4") (pintype "passive"))
      (node (ref "S40") (pin "4") (pinfunction "P1_4") (pintype "passive"))
      (node (ref "S48") (pin "4") (pinfunction "P1_4") (pintype "passive"))
      (node (ref "S56") (pin "4") (pinfunction "P1_4") (pintype "passive"))
      (node (ref "S64") (pin "4") (pinfunction "P1_4") (pintype "passive"))
      (node (ref "S8") (pin "4") (pinfunction "P1_4") (pintype "passive"))
      (node (ref "U$10") (pin "9") (pinfunction "9_9") (pintype "passive"))
    )
    (net (code "54") (name "Net-(S17-S)") (class "Default")
      (node (ref "S17") (pin "1") (pinfunction "S_1") (pintype "passive"))
      (node (ref "S18") (pin "1") (pinfunction "S_1") (pintype "passive"))
      (node (ref "S19") (pin "1") (pinfunction "S_1") (pintype "passive"))
      (node (ref "S20") (pin "1") (pinfunction "S_1") (pintype "passive"))
      (node (ref "S21") (pin "1") (pinfunction "S_1") (pintype "passive"))
      (node (ref "S22") (pin "1") (pinfunction "S_1") (pintype "passive"))
      (node (ref "S23") (pin "1") (pinfunction "S_1") (pintype "passive"))
      (node (ref "S24") (pin "1") (pinfunction "S_1") (pintype "passive"))
      (node (ref "U$9") (pin "4") (pinfunction "4_4") (pintype "passive"))
    )
    (net (code "55") (name "Net-(S25-S)") (class "Default")
      (node (ref "S25") (pin "1") (pinfunction "S_1") (pintype "passive"))
      (node (ref "S26") (pin "1") (pinfunction "S_1") (pintype "passive"))
      (node (ref "S27") (pin "1") (pinfunction "S_1") (pintype "passive"))
      (node (ref "S28") (pin "1") (pinfunction "S_1") (pintype "passive"))
      (node (ref "S29") (pin "1") (pinfunction "S_1") (pintype "passive"))
      (node (ref "S30") (pin "1") (pinfunction "S_1") (pintype "passive"))
      (node (ref "S31") (pin "1") (pinfunction "S_1") (pintype "passive"))
      (node (ref "S32") (pin "1") (pinfunction "S_1") (pintype "passive"))
      (node (ref "U$9") (pin "5") (pinfunction "5_5") (pintype "passive"))
    )
    (net (code "56") (name "Net-(S33-S)") (class "Default")
      (node (ref "S33") (pin "1") (pinfunction "S_1") (pintype "passive"))
      (node (ref "S34") (pin "1") (pinfunction "S_1") (pintype "passive"))
      (node (ref "S35") (pin "1") (pinfunction "S_1") (pintype "passive"))
      (node (ref "S36") (pin "1") (pinfunction "S_1") (pintype "passive"))
      (node (ref "S37") (pin "1") (pinfunction "S_1") (pintype "passive"))
      (node (ref "S38") (pin "1") (pinfunction "S_1") (pintype "passive"))
      (node (ref "S39") (pin "1") (pinfunction "S_1") (pintype "passive"))
      (node (ref "S40") (pin "1") (pinfunction "S_1") (pintype "passive"))
      (node (ref "U$9") (pin "6") (pinfunction "6_6") (pintype "passive"))
    )
    (net (code "57") (name "Net-(S41-S)") (class "Default")
      (node (ref "S41") (pin "1") (pinfunction "S_1") (pintype "passive"))
      (node (ref "S42") (pin "1") (pinfunction "S_1") (pintype "passive"))
      (node (ref "S43") (pin "1") (pinfunction "S_1") (pintype "passive"))
      (node (ref "S44") (pin "1") (pinfunction "S_1") (pintype "passive"))
      (node (ref "S45") (pin "1") (pinfunction "S_1") (pintype "passive"))
      (node (ref "S46") (pin "1") (pinfunction "S_1") (pintype "passive"))
      (node (ref "S47") (pin "1") (pinfunction "S_1") (pintype "passive"))
      (node (ref "S48") (pin "1") (pinfunction "S_1") (pintype "passive"))
      (node (ref "U$9") (pin "7") (pinfunction "7_7") (pintype "passive"))
    )
    (net (code "58") (name "Net-(S49-S)") (class "Default")
      (node (ref "S49") (pin "1") (pinfunction "S_1") (pintype "passive"))
      (node (ref "S50") (pin "1") (pinfunction "S_1") (pintype "passive"))
      (node (ref "S51") (pin "1") (pinfunction "S_1") (pintype "passive"))
      (node (ref "S52") (pin "1") (pinfunction "S_1") (pintype "passive"))
      (node (ref "S53") (pin "1") (pinfunction "S_1") (pintype "passive"))
      (node (ref "S54") (pin "1") (pinfunction "S_1") (pintype "passive"))
      (node (ref "S55") (pin "1") (pinfunction "S_1") (pintype "passive"))
      (node (ref "S56") (pin "1") (pinfunction "S_1") (pintype "passive"))
      (node (ref "U$9") (pin "8") (pinfunction "8_8") (pintype "passive"))
    )
    (net (code "59") (name "Net-(S57-S)") (class "Default")
      (node (ref "S57") (pin "1") (pinfunction "S_1") (pintype "passive"))
      (node (ref "S58") (pin "1") (pinfunction "S_1") (pintype "passive"))
      (node (ref "S59") (pin "1") (pinfunction "S_1") (pintype "passive"))
      (node (ref "S60") (pin "1") (pinfunction "S_1") (pintype "passive"))
      (node (ref "S61") (pin "1") (pinfunction "S_1") (pintype "passive"))
      (node (ref "S62") (pin "1") (pinfunction "S_1") (pintype "passive"))
      (node (ref "S63") (pin "1") (pinfunction "S_1") (pintype "passive"))
      (node (ref "S64") (pin "1") (pinfunction "S_1") (pintype "passive"))
      (node (ref "U$9") (pin "9") (pinfunction "9_9") (pintype "passive"))
    )
    (net (code "60") (name "Net-(T1-B)") (class "Default")
      (node (ref "T1") (pin "2") (pinfunction "B_2") (pintype "passive"))
      (node (ref "U$8") (pin "9") (pinfunction "9_9") (pintype "passive"))
    )
    (net (code "61") (name "Net-(T1-C)") (class "Default")
      (node (ref "DIS1") (pin "8") (pinfunction "CC_8") (pintype "passive"))
      (node (ref "T1") (pin "3") (pinfunction "C_3") (pintype "passive"))
    )
    (net (code "62") (name "Net-(T2-B)") (class "Default")
      (node (ref "T2") (pin "2") (pinfunction "B_2") (pintype "passive"))
      (node (ref "U$8") (pin "8") (pinfunction "8_8") (pintype "passive"))
    )
    (net (code "63") (name "Net-(T2-C)") (class "Default")
      (node (ref "DIS2") (pin "8") (pinfunction "CC_8") (pintype "passive"))
      (node (ref "T2") (pin "3") (pinfunction "C_3") (pintype "passive"))
    )
    (net (code "64") (name "Net-(T3-B)") (class "Default")
      (node (ref "T3") (pin "2") (pinfunction "B_2") (pintype "passive"))
      (node (ref "U$8") (pin "7") (pinfunction "7_7") (pintype "passive"))
    )
    (net (code "65") (name "Net-(T3-C)") (class "Default")
      (node (ref "DIS3") (pin "8") (pinfunction "CC_8") (pintype "passive"))
      (node (ref "T3") (pin "3") (pinfunction "C_3") (pintype "passive"))
    )
    (net (code "66") (name "Net-(T4-B)") (class "Default")
      (node (ref "T4") (pin "2") (pinfunction "B_2") (pintype "passive"))
      (node (ref "U$8") (pin "6") (pinfunction "6_6") (pintype "passive"))
    )
    (net (code "67") (name "Net-(T4-C)") (class "Default")
      (node (ref "DIS4") (pin "8") (pinfunction "CC_8") (pintype "passive"))
      (node (ref "T4") (pin "3") (pinfunction "C_3") (pintype "passive"))
    )
    (net (code "68") (name "Net-(X1-DB0)") (class "Default")
      (node (ref "U$1") (pin "9") (pinfunction "9_9") (pintype "passive"))
      (node (ref "X1") (pin "7") (pinfunction "DB0_7") (pintype "bidirectional"))
    )
    (net (code "69") (name "Net-(X1-DB1)") (class "Default")
      (node (ref "U$1") (pin "8") (pinfunction "8_8") (pintype "passive"))
      (node (ref "X1") (pin "8") (pinfunction "DB1_8") (pintype "bidirectional"))
    )
    (net (code "70") (name "Net-(X1-DB2)") (class "Default")
      (node (ref "U$1") (pin "7") (pinfunction "7_7") (pintype "passive"))
      (node (ref "X1") (pin "9") (pinfunction "DB2_9") (pintype "bidirectional"))
    )
    (net (code "71") (name "Net-(X1-DB3)") (class "Default")
      (node (ref "U$1") (pin "6") (pinfunction "6_6") (pintype "passive"))
      (node (ref "X1") (pin "10") (pinfunction "DB3_10") (pintype "bidirectional"))
    )
    (net (code "72") (name "Net-(X1-DB4)") (class "Default")
      (node (ref "U$1") (pin "5") (pinfunction "5_5") (pintype "passive"))
      (node (ref "X1") (pin "11") (pinfunction "DB4_11") (pintype "bidirectional"))
    )
    (net (code "73") (name "Net-(X1-DB5)") (class "Default")
      (node (ref "U$1") (pin "4") (pinfunction "4_4") (pintype "passive"))
      (node (ref "X1") (pin "12") (pinfunction "DB5_12") (pintype "bidirectional"))
    )
    (net (code "74") (name "Net-(X1-DB6)") (class "Default")
      (node (ref "U$1") (pin "3") (pinfunction "3_3") (pintype "passive"))
      (node (ref "X1") (pin "13") (pinfunction "DB6_13") (pintype "bidirectional"))
    )
    (net (code "75") (name "Net-(X1-DB7)") (class "Default")
      (node (ref "U$1") (pin "2") (pinfunction "2_2") (pintype "passive"))
      (node (ref "X1") (pin "14") (pinfunction "DB7_14") (pintype "bidirectional"))
    )
    (net (code "76") (name "Net-(X1-E)") (class "Default")
      (node (ref "U$6") (pin "2") (pinfunction "2_2") (pintype "passive"))
      (node (ref "X1") (pin "6") (pinfunction "E_6") (pintype "input"))
    )
    (net (code "77") (name "Net-(X1-RS)") (class "Default")
      (node (ref "U$6") (pin "3") (pinfunction "3_3") (pintype "passive"))
      (node (ref "X1") (pin "4") (pinfunction "RS_4") (pintype "input"))
    )
    (net (code "78") (name "VCC") (class "Default")
      (node (ref "C1") (pin "+") (pinfunction "+_+") (pintype "passive"))
      (node (ref "IC1") (pin "29") (pinfunction "~{PSEN}_29") (pintype "output"))
      (node (ref "IC1") (pin "31") (pinfunction "~{EA}/VPP_31") (pintype "input"))
      (node (ref "IC1") (pin "40") (pinfunction "VCC_40") (pintype "power_in"))
      (node (ref "J1") (pin "2") (pinfunction "S_2") (pintype "passive"))
      (node (ref "SV1") (pin "4") (pinfunction "4_4") (pintype "passive"))
      (node (ref "SV2") (pin "4") (pinfunction "4_4") (pintype "passive"))
      (node (ref "SV3") (pin "4") (pinfunction "4_4") (pintype "passive"))
      (node (ref "SV4") (pin "4") (pinfunction "4_4") (pintype "passive"))
      (node (ref "U$2") (pin "10") (pinfunction "10_10") (pintype "passive"))
      (node (ref "U$3") (pin "10") (pinfunction "10_10") (pintype "passive"))
      (node (ref "U$4") (pin "10") (pinfunction "10_10") (pintype "passive"))
      (node (ref "U$5") (pin "10") (pinfunction "10_10") (pintype "passive"))
      (node (ref "X1") (pin "15") (pinfunction "A_15") (pintype "input"))
      (node (ref "X1") (pin "2") (pinfunction "VDD_2") (pintype "power_in"))
    )
    (net (code "79") (name "unconnected-(DIS1-CC-Pad3)") (class "Default")
      (node (ref "DIS1") (pin "3") (pinfunction "CC_3") (pintype "passive"))
    )
    (net (code "80") (name "unconnected-(DIS1-DP-Pad5)") (class "Default")
      (node (ref "DIS1") (pin "5") (pinfunction "DP_5") (pintype "passive"))
    )
    (net (code "81") (name "unconnected-(DIS2-CC-Pad3)") (class "Default")
      (node (ref "DIS2") (pin "3") (pinfunction "CC_3") (pintype "passive"))
    )
    (net (code "82") (name "unconnected-(DIS2-DP-Pad5)") (class "Default")
      (node (ref "DIS2") (pin "5") (pinfunction "DP_5") (pintype "passive"))
    )
    (net (code "83") (name "unconnected-(DIS3-CC-Pad3)") (class "Default")
      (node (ref "DIS3") (pin "3") (pinfunction "CC_3") (pintype "passive"))
    )
    (net (code "84") (name "unconnected-(DIS3-DP-Pad5)") (class "Default")
      (node (ref "DIS3") (pin "5") (pinfunction "DP_5") (pintype "passive"))
    )
    (net (code "85") (name "unconnected-(DIS4-A-Pad7)") (class "Default")
      (node (ref "DIS4") (pin "7") (pinfunction "A_7") (pintype "passive"))
    )
    (net (code "86") (name "unconnected-(DIS4-CC-Pad3)") (class "Default")
      (node (ref "DIS4") (pin "3") (pinfunction "CC_3") (pintype "passive"))
    )
    (net (code "87") (name "unconnected-(DIS4-DP-Pad5)") (class "Default")
      (node (ref "DIS4") (pin "5") (pinfunction "DP_5") (pintype "passive"))
    )
    (net (code "88") (name "unconnected-(IC1-ALE{slash}~{PROG}-Pad30)") (class "Default")
      (node (ref "IC1") (pin "30") (pinfunction "ALE/~{PROG}_30") (pintype "output"))
    )
    (net (code "89") (name "unconnected-(S1-P-Pad3)") (class "Default")
      (node (ref "S1") (pin "3") (pinfunction "P_3") (pintype "passive"))
    )
    (net (code "90") (name "unconnected-(S1-S1-Pad2)") (class "Default")
      (node (ref "S1") (pin "2") (pinfunction "S1_2") (pintype "passive"))
    )
    (net (code "91") (name "unconnected-(S2-P-Pad3)") (class "Default")
      (node (ref "S2") (pin "3") (pinfunction "P_3") (pintype "passive"))
    )
    (net (code "92") (name "unconnected-(S2-S1-Pad2)") (class "Default")
      (node (ref "S2") (pin "2") (pinfunction "S1_2") (pintype "passive"))
    )
    (net (code "93") (name "unconnected-(S3-P-Pad3)") (class "Default")
      (node (ref "S3") (pin "3") (pinfunction "P_3") (pintype "passive"))
    )
    (net (code "94") (name "unconnected-(S3-S1-Pad2)") (class "Default")
      (node (ref "S3") (pin "2") (pinfunction "S1_2") (pintype "passive"))
    )
    (net (code "95") (name "unconnected-(S4-P-Pad3)") (class "Default")
      (node (ref "S4") (pin "3") (pinfunction "P_3") (pintype "passive"))
    )
    (net (code "96") (name "unconnected-(S4-S1-Pad2)") (class "Default")
      (node (ref "S4") (pin "2") (pinfunction "S1_2") (pintype "passive"))
    )
    (net (code "97") (name "unconnected-(S5-P-Pad3)") (class "Default")
      (node (ref "S5") (pin "3") (pinfunction "P_3") (pintype "passive"))
    )
    (net (code "98") (name "unconnected-(S5-S1-Pad2)") (class "Default")
      (node (ref "S5") (pin "2") (pinfunction "S1_2") (pintype "passive"))
    )
    (net (code "99") (name "unconnected-(S6-P-Pad3)") (class "Default")
      (node (ref "S6") (pin "3") (pinfunction "P_3") (pintype "passive"))
    )
    (net (code "100") (name "unconnected-(S6-S1-Pad2)") (class "Default")
      (node (ref "S6") (pin "2") (pinfunction "S1_2") (pintype "passive"))
    )
    (net (code "101") (name "unconnected-(S7-P-Pad3)") (class "Default")
      (node (ref "S7") (pin "3") (pinfunction "P_3") (pintype "passive"))
    )
    (net (code "102") (name "unconnected-(S7-S1-Pad2)") (class "Default")
      (node (ref "S7") (pin "2") (pinfunction "S1_2") (pintype "passive"))
    )
    (net (code "103") (name "unconnected-(S8-P-Pad3)") (class "Default")
      (node (ref "S8") (pin "3") (pinfunction "P_3") (pintype "passive"))
    )
    (net (code "104") (name "unconnected-(S8-S1-Pad2)") (class "Default")
      (node (ref "S8") (pin "2") (pinfunction "S1_2") (pintype "passive"))
    )
    (net (code "105") (name "unconnected-(S9-P-Pad3)") (class "Default")
      (node (ref "S9") (pin "3") (pinfunction "P_3") (pintype "passive"))
    )
    (net (code "106") (name "unconnected-(S9-S1-Pad2)") (class "Default")
      (node (ref "S9") (pin "2") (pinfunction "S1_2") (pintype "passive"))
    )
    (net (code "107") (name "unconnected-(S10-P-Pad3)") (class "Default")
      (node (ref "S10") (pin "3") (pinfunction "P_3") (pintype "passive"))
    )
    (net (code "108") (name "unconnected-(S10-S1-Pad2)") (class "Default")
      (node (ref "S10") (pin "2") (pinfunction "S1_2") (pintype "passive"))
    )
    (net (code "109") (name "unconnected-(S11-P-Pad3)") (class "Default")
      (node (ref "S11") (pin "3") (pinfunction "P_3") (pintype "passive"))
    )
    (net (code "110") (name "unconnected-(S11-S1-Pad2)") (class "Default")
      (node (ref "S11") (pin "2") (pinfunction "S1_2") (pintype "passive"))
    )
    (net (code "111") (name "unconnected-(S12-P-Pad3)") (class "Default")
      (node (ref "S12") (pin "3") (pinfunction "P_3") (pintype "passive"))
    )
    (net (code "112") (name "unconnected-(S12-S1-Pad2)") (class "Default")
      (node (ref "S12") (pin "2") (pinfunction "S1_2") (pintype "passive"))
    )
    (net (code "113") (name "unconnected-(S13-P-Pad3)") (class "Default")
      (node (ref "S13") (pin "3") (pinfunction "P_3") (pintype "passive"))
    )
    (net (code "114") (name "unconnected-(S13-S1-Pad2)") (class "Default")
      (node (ref "S13") (pin "2") (pinfunction "S1_2") (pintype "passive"))
    )
    (net (code "115") (name "unconnected-(S14-P-Pad3)") (class "Default")
      (node (ref "S14") (pin "3") (pinfunction "P_3") (pintype "passive"))
    )
    (net (code "116") (name "unconnected-(S14-S1-Pad2)") (class "Default")
      (node (ref "S14") (pin "2") (pinfunction "S1_2") (pintype "passive"))
    )
    (net (code "117") (name "unconnected-(S15-P-Pad3)") (class "Default")
      (node (ref "S15") (pin "3") (pinfunction "P_3") (pintype "passive"))
    )
    (net (code "118") (name "unconnected-(S15-S1-Pad2)") (class "Default")
      (node (ref "S15") (pin "2") (pinfunction "S1_2") (pintype "passive"))
    )
    (net (code "119") (name "unconnected-(S16-P-Pad3)") (class "Default")
      (node (ref "S16") (pin "3") (pinfunction "P_3") (pintype "passive"))
    )
    (net (code "120") (name "unconnected-(S16-S1-Pad2)") (class "Default")
      (node (ref "S16") (pin "2") (pinfunction "S1_2") (pintype "passive"))
    )
    (net (code "121") (name "unconnected-(S17-P-Pad3)") (class "Default")
      (node (ref "S17") (pin "3") (pinfunction "P_3") (pintype "passive"))
    )
    (net (code "122") (name "unconnected-(S17-S1-Pad2)") (class "Default")
      (node (ref "S17") (pin "2") (pinfunction "S1_2") (pintype "passive"))
    )
    (net (code "123") (name "unconnected-(S18-P-Pad3)") (class "Default")
      (node (ref "S18") (pin "3") (pinfunction "P_3") (pintype "passive"))
    )
    (net (code "124") (name "unconnected-(S18-S1-Pad2)") (class "Default")
      (node (ref "S18") (pin "2") (pinfunction "S1_2") (pintype "passive"))
    )
    (net (code "125") (name "unconnected-(S19-P-Pad3)") (class "Default")
      (node (ref "S19") (pin "3") (pinfunction "P_3") (pintype "passive"))
    )
    (net (code "126") (name "unconnected-(S19-S1-Pad2)") (class "Default")
      (node (ref "S19") (pin "2") (pinfunction "S1_2") (pintype "passive"))
    )
    (net (code "127") (name "unconnected-(S20-P-Pad3)") (class "Default")
      (node (ref "S20") (pin "3") (pinfunction "P_3") (pintype "passive"))
    )
    (net (code "128") (name "unconnected-(S20-S1-Pad2)") (class "Default")
      (node (ref "S20") (pin "2") (pinfunction "S1_2") (pintype "passive"))
    )
    (net (code "129") (name "unconnected-(S21-P-Pad3)") (class "Default")
      (node (ref "S21") (pin "3") (pinfunction "P_3") (pintype "passive"))
    )
    (net (code "130") (name "unconnected-(S21-S1-Pad2)") (class "Default")
      (node (ref "S21") (pin "2") (pinfunction "S1_2") (pintype "passive"))
    )
    (net (code "131") (name "unconnected-(S22-P-Pad3)") (class "Default")
      (node (ref "S22") (pin "3") (pinfunction "P_3") (pintype "passive"))
    )
    (net (code "132") (name "unconnected-(S22-S1-Pad2)") (class "Default")
      (node (ref "S22") (pin "2") (pinfunction "S1_2") (pintype "passive"))
    )
    (net (code "133") (name "unconnected-(S23-P-Pad3)") (class "Default")
      (node (ref "S23") (pin "3") (pinfunction "P_3") (pintype "passive"))
    )
    (net (code "134") (name "unconnected-(S23-S1-Pad2)") (class "Default")
      (node (ref "S23") (pin "2") (pinfunction "S1_2") (pintype "passive"))
    )
    (net (code "135") (name "unconnected-(S24-P-Pad3)") (class "Default")
      (node (ref "S24") (pin "3") (pinfunction "P_3") (pintype "passive"))
    )
    (net (code "136") (name "unconnected-(S24-S1-Pad2)") (class "Default")
      (node (ref "S24") (pin "2") (pinfunction "S1_2") (pintype "passive"))
    )
    (net (code "137") (name "unconnected-(S25-P-Pad3)") (class "Default")
      (node (ref "S25") (pin "3") (pinfunction "P_3") (pintype "passive"))
    )
    (net (code "138") (name "unconnected-(S25-S1-Pad2)") (class "Default")
      (node (ref "S25") (pin "2") (pinfunction "S1_2") (pintype "passive"))
    )
    (net (code "139") (name "unconnected-(S26-P-Pad3)") (class "Default")
      (node (ref "S26") (pin "3") (pinfunction "P_3") (pintype "passive"))
    )
    (net (code "140") (name "unconnected-(S26-S1-Pad2)") (class "Default")
      (node (ref "S26") (pin "2") (pinfunction "S1_2") (pintype "passive"))
    )
    (net (code "141") (name "unconnected-(S27-P-Pad3)") (class "Default")
      (node (ref "S27") (pin "3") (pinfunction "P_3") (pintype "passive"))
    )
    (net (code "142") (name "unconnected-(S27-S1-Pad2)") (class "Default")
      (node (ref "S27") (pin "2") (pinfunction "S1_2") (pintype "passive"))
    )
    (net (code "143") (name "unconnected-(S28-P-Pad3)") (class "Default")
      (node (ref "S28") (pin "3") (pinfunction "P_3") (pintype "passive"))
    )
    (net (code "144") (name "unconnected-(S28-S1-Pad2)") (class "Default")
      (node (ref "S28") (pin "2") (pinfunction "S1_2") (pintype "passive"))
    )
    (net (code "145") (name "unconnected-(S29-P-Pad3)") (class "Default")
      (node (ref "S29") (pin "3") (pinfunction "P_3") (pintype "passive"))
    )
    (net (code "146") (name "unconnected-(S29-S1-Pad2)") (class "Default")
      (node (ref "S29") (pin "2") (pinfunction "S1_2") (pintype "passive"))
    )
    (net (code "147") (name "unconnected-(S30-P-Pad3)") (class "Default")
      (node (ref "S30") (pin "3") (pinfunction "P_3") (pintype "passive"))
    )
    (net (code "148") (name "unconnected-(S30-S1-Pad2)") (class "Default")
      (node (ref "S30") (pin "2") (pinfunction "S1_2") (pintype "passive"))
    )
    (net (code "149") (name "unconnected-(S31-P-Pad3)") (class "Default")
      (node (ref "S31") (pin "3") (pinfunction "P_3") (pintype "passive"))
    )
    (net (code "150") (name "unconnected-(S31-S1-Pad2)") (class "Default")
      (node (ref "S31") (pin "2") (pinfunction "S1_2") (pintype "passive"))
    )
    (net (code "151") (name "unconnected-(S32-P-Pad3)") (class "Default")
      (node (ref "S32") (pin "3") (pinfunction "P_3") (pintype "passive"))
    )
    (net (code "152") (name "unconnected-(S32-S1-Pad2)") (class "Default")
      (node (ref "S32") (pin "2") (pinfunction "S1_2") (pintype "passive"))
    )
    (net (code "153") (name "unconnected-(S33-P-Pad3)") (class "Default")
      (node (ref "S33") (pin "3") (pinfunction "P_3") (pintype "passive"))
    )
    (net (code "154") (name "unconnected-(S33-S1-Pad2)") (class "Default")
      (node (ref "S33") (pin "2") (pinfunction "S1_2") (pintype "passive"))
    )
    (net (code "155") (name "unconnected-(S34-P-Pad3)") (class "Default")
      (node (ref "S34") (pin "3") (pinfunction "P_3") (pintype "passive"))
    )
    (net (code "156") (name "unconnected-(S34-S1-Pad2)") (class "Default")
      (node (ref "S34") (pin "2") (pinfunction "S1_2") (pintype "passive"))
    )
    (net (code "157") (name "unconnected-(S35-P-Pad3)") (class "Default")
      (node (ref "S35") (pin "3") (pinfunction "P_3") (pintype "passive"))
    )
    (net (code "158") (name "unconnected-(S35-S1-Pad2)") (class "Default")
      (node (ref "S35") (pin "2") (pinfunction "S1_2") (pintype "passive"))
    )
    (net (code "159") (name "unconnected-(S36-P-Pad3)") (class "Default")
      (node (ref "S36") (pin "3") (pinfunction "P_3") (pintype "passive"))
    )
    (net (code "160") (name "unconnected-(S36-S1-Pad2)") (class "Default")
      (node (ref "S36") (pin "2") (pinfunction "S1_2") (pintype "passive"))
    )
    (net (code "161") (name "unconnected-(S37-P-Pad3)") (class "Default")
      (node (ref "S37") (pin "3") (pinfunction "P_3") (pintype "passive"))
    )
    (net (code "162") (name "unconnected-(S37-S1-Pad2)") (class "Default")
      (node (ref "S37") (pin "2") (pinfunction "S1_2") (pintype "passive"))
    )
    (net (code "163") (name "unconnected-(S38-P-Pad3)") (class "Default")
      (node (ref "S38") (pin "3") (pinfunction "P_3") (pintype "passive"))
    )
    (net (code "164") (name "unconnected-(S38-S1-Pad2)") (class "Default")
      (node (ref "S38") (pin "2") (pinfunction "S1_2") (pintype "passive"))
    )
    (net (code "165") (name "unconnected-(S39-P-Pad3)") (class "Default")
      (node (ref "S39") (pin "3") (pinfunction "P_3") (pintype "passive"))
    )
    (net (code "166") (name "unconnected-(S39-S1-Pad2)") (class "Default")
      (node (ref "S39") (pin "2") (pinfunction "S1_2") (pintype "passive"))
    )
    (net (code "167") (name "unconnected-(S40-P-Pad3)") (class "Default")
      (node (ref "S40") (pin "3") (pinfunction "P_3") (pintype "passive"))
    )
    (net (code "168") (name "unconnected-(S40-S1-Pad2)") (class "Default")
      (node (ref "S40") (pin "2") (pinfunction "S1_2") (pintype "passive"))
    )
    (net (code "169") (name "unconnected-(S41-P-Pad3)") (class "Default")
      (node (ref "S41") (pin "3") (pinfunction "P_3") (pintype "passive"))
    )
    (net (code "170") (name "unconnected-(S41-S1-Pad2)") (class "Default")
      (node (ref "S41") (pin "2") (pinfunction "S1_2") (pintype "passive"))
    )
    (net (code "171") (name "unconnected-(S42-P-Pad3)") (class "Default")
      (node (ref "S42") (pin "3") (pinfunction "P_3") (pintype "passive"))
    )
    (net (code "172") (name "unconnected-(S42-S1-Pad2)") (class "Default")
      (node (ref "S42") (pin "2") (pinfunction "S1_2") (pintype "passive"))
    )
    (net (code "173") (name "unconnected-(S43-P-Pad3)") (class "Default")
      (node (ref "S43") (pin "3") (pinfunction "P_3") (pintype "passive"))
    )
    (net (code "174") (name "unconnected-(S43-S1-Pad2)") (class "Default")
      (node (ref "S43") (pin "2") (pinfunction "S1_2") (pintype "passive"))
    )
    (net (code "175") (name "unconnected-(S44-P-Pad3)") (class "Default")
      (node (ref "S44") (pin "3") (pinfunction "P_3") (pintype "passive"))
    )
    (net (code "176") (name "unconnected-(S44-S1-Pad2)") (class "Default")
      (node (ref "S44") (pin "2") (pinfunction "S1_2") (pintype "passive"))
    )
    (net (code "177") (name "unconnected-(S45-P-Pad3)") (class "Default")
      (node (ref "S45") (pin "3") (pinfunction "P_3") (pintype "passive"))
    )
    (net (code "178") (name "unconnected-(S45-S1-Pad2)") (class "Default")
      (node (ref "S45") (pin "2") (pinfunction "S1_2") (pintype "passive"))
    )
    (net (code "179") (name "unconnected-(S46-P-Pad3)") (class "Default")
      (node (ref "S46") (pin "3") (pinfunction "P_3") (pintype "passive"))
    )
    (net (code "180") (name "unconnected-(S46-S1-Pad2)") (class "Default")
      (node (ref "S46") (pin "2") (pinfunction "S1_2") (pintype "passive"))
    )
    (net (code "181") (name "unconnected-(S47-P-Pad3)") (class "Default")
      (node (ref "S47") (pin "3") (pinfunction "P_3") (pintype "passive"))
    )
    (net (code "182") (name "unconnected-(S47-S1-Pad2)") (class "Default")
      (node (ref "S47") (pin "2") (pinfunction "S1_2") (pintype "passive"))
    )
    (net (code "183") (name "unconnected-(S48-P-Pad3)") (class "Default")
      (node (ref "S48") (pin "3") (pinfunction "P_3") (pintype "passive"))
    )
    (net (code "184") (name "unconnected-(S48-S1-Pad2)") (class "Default")
      (node (ref "S48") (pin "2") (pinfunction "S1_2") (pintype "passive"))
    )
    (net (code "185") (name "unconnected-(S49-P-Pad3)") (class "Default")
      (node (ref "S49") (pin "3") (pinfunction "P_3") (pintype "passive"))
    )
    (net (code "186") (name "unconnected-(S49-S1-Pad2)") (class "Default")
      (node (ref "S49") (pin "2") (pinfunction "S1_2") (pintype "passive"))
    )
    (net (code "187") (name "unconnected-(S50-P-Pad3)") (class "Default")
      (node (ref "S50") (pin "3") (pinfunction "P_3") (pintype "passive"))
    )
    (net (code "188") (name "unconnected-(S50-S1-Pad2)") (class "Default")
      (node (ref "S50") (pin "2") (pinfunction "S1_2") (pintype "passive"))
    )
    (net (code "189") (name "unconnected-(S51-P-Pad3)") (class "Default")
      (node (ref "S51") (pin "3") (pinfunction "P_3") (pintype "passive"))
    )
    (net (code "190") (name "unconnected-(S51-S1-Pad2)") (class "Default")
      (node (ref "S51") (pin "2") (pinfunction "S1_2") (pintype "passive"))
    )
    (net (code "191") (name "unconnected-(S52-P-Pad3)") (class "Default")
      (node (ref "S52") (pin "3") (pinfunction "P_3") (pintype "passive"))
    )
    (net (code "192") (name "unconnected-(S52-S1-Pad2)") (class "Default")
      (node (ref "S52") (pin "2") (pinfunction "S1_2") (pintype "passive"))
    )
    (net (code "193") (name "unconnected-(S53-P-Pad3)") (class "Default")
      (node (ref "S53") (pin "3") (pinfunction "P_3") (pintype "passive"))
    )
    (net (code "194") (name "unconnected-(S53-S1-Pad2)") (class "Default")
      (node (ref "S53") (pin "2") (pinfunction "S1_2") (pintype "passive"))
    )
    (net (code "195") (name "unconnected-(S54-P-Pad3)") (class "Default")
      (node (ref "S54") (pin "3") (pinfunction "P_3") (pintype "passive"))
    )
    (net (code "196") (name "unconnected-(S54-S1-Pad2)") (class "Default")
      (node (ref "S54") (pin "2") (pinfunction "S1_2") (pintype "passive"))
    )
    (net (code "197") (name "unconnected-(S55-P-Pad3)") (class "Default")
      (node (ref "S55") (pin "3") (pinfunction "P_3") (pintype "passive"))
    )
    (net (code "198") (name "unconnected-(S55-S1-Pad2)") (class "Default")
      (node (ref "S55") (pin "2") (pinfunction "S1_2") (pintype "passive"))
    )
    (net (code "199") (name "unconnected-(S56-P-Pad3)") (class "Default")
      (node (ref "S56") (pin "3") (pinfunction "P_3") (pintype "passive"))
    )
    (net (code "200") (name "unconnected-(S56-S1-Pad2)") (class "Default")
      (node (ref "S56") (pin "2") (pinfunction "S1_2") (pintype "passive"))
    )
    (net (code "201") (name "unconnected-(S57-P-Pad3)") (class "Default")
      (node (ref "S57") (pin "3") (pinfunction "P_3") (pintype "passive"))
    )
    (net (code "202") (name "unconnected-(S57-S1-Pad2)") (class "Default")
      (node (ref "S57") (pin "2") (pinfunction "S1_2") (pintype "passive"))
    )
    (net (code "203") (name "unconnected-(S58-P-Pad3)") (class "Default")
      (node (ref "S58") (pin "3") (pinfunction "P_3") (pintype "passive"))
    )
    (net (code "204") (name "unconnected-(S58-S1-Pad2)") (class "Default")
      (node (ref "S58") (pin "2") (pinfunction "S1_2") (pintype "passive"))
    )
    (net (code "205") (name "unconnected-(S59-P-Pad3)") (class "Default")
      (node (ref "S59") (pin "3") (pinfunction "P_3") (pintype "passive"))
    )
    (net (code "206") (name "unconnected-(S59-S1-Pad2)") (class "Default")
      (node (ref "S59") (pin "2") (pinfunction "S1_2") (pintype "passive"))
    )
    (net (code "207") (name "unconnected-(S60-P-Pad3)") (class "Default")
      (node (ref "S60") (pin "3") (pinfunction "P_3") (pintype "passive"))
    )
    (net (code "208") (name "unconnected-(S60-S1-Pad2)") (class "Default")
      (node (ref "S60") (pin "2") (pinfunction "S1_2") (pintype "passive"))
    )
    (net (code "209") (name "unconnected-(S61-P-Pad3)") (class "Default")
      (node (ref "S61") (pin "3") (pinfunction "P_3") (pintype "passive"))
    )
    (net (code "210") (name "unconnected-(S61-S1-Pad2)") (class "Default")
      (node (ref "S61") (pin "2") (pinfunction "S1_2") (pintype "passive"))
    )
    (net (code "211") (name "unconnected-(S62-P-Pad3)") (class "Default")
      (node (ref "S62") (pin "3") (pinfunction "P_3") (pintype "passive"))
    )
    (net (code "212") (name "unconnected-(S62-S1-Pad2)") (class "Default")
      (node (ref "S62") (pin "2") (pinfunction "S1_2") (pintype "passive"))
    )
    (net (code "213") (name "unconnected-(S63-P-Pad3)") (class "Default")
      (node (ref "S63") (pin "3") (pinfunction "P_3") (pintype "passive"))
    )
    (net (code "214") (name "unconnected-(S63-S1-Pad2)") (class "Default")
      (node (ref "S63") (pin "2") (pinfunction "S1_2") (pintype "passive"))
    )
    (net (code "215") (name "unconnected-(S64-P-Pad3)") (class "Default")
      (node (ref "S64") (pin "3") (pinfunction "P_3") (pintype "passive"))
    )
    (net (code "216") (name "unconnected-(S64-S1-Pad2)") (class "Default")
      (node (ref "S64") (pin "2") (pinfunction "S1_2") (pintype "passive"))
    )
    (net (code "217") (name "unconnected-(U$1-Pad1)") (class "Default")
      (node (ref "U$1") (pin "1") (pinfunction "1_1") (pintype "passive"))
    )
    (net (code "218") (name "unconnected-(U$1-Pad10)") (class "Default")
      (node (ref "U$1") (pin "10") (pinfunction "10_10") (pintype "passive"))
    )
    (net (code "219") (name "unconnected-(U$6-Pad1)") (class "Default")
      (node (ref "U$6") (pin "1") (pinfunction "1_1") (pintype "passive"))
    )
    (net (code "220") (name "unconnected-(U$6-Pad4)") (class "Default")
      (node (ref "U$6") (pin "4") (pinfunction "4_4") (pintype "passive"))
    )
    (net (code "221") (name "unconnected-(U$6-Pad5)") (class "Default")
      (node (ref "U$6") (pin "5") (pinfunction "5_5") (pintype "passive"))
    )
    (net (code "222") (name "unconnected-(U$6-Pad6)") (class "Default")
      (node (ref "U$6") (pin "6") (pinfunction "6_6") (pintype "passive"))
    )
    (net (code "223") (name "unconnected-(U$6-Pad7)") (class "Default")
      (node (ref "U$6") (pin "7") (pinfunction "7_7") (pintype "passive"))
    )
    (net (code "224") (name "unconnected-(U$6-Pad8)") (class "Default")
      (node (ref "U$6") (pin "8") (pinfunction "8_8") (pintype "passive"))
    )
    (net (code "225") (name "unconnected-(U$6-Pad9)") (class "Default")
      (node (ref "U$6") (pin "9") (pinfunction "9_9") (pintype "passive"))
    )
    (net (code "226") (name "unconnected-(U$6-Pad10)") (class "Default")
      (node (ref "U$6") (pin "10") (pinfunction "10_10") (pintype "passive"))
    )
    (net (code "227") (name "unconnected-(U$7-Pad1)") (class "Default")
      (node (ref "U$7") (pin "1") (pinfunction "1_1") (pintype "passive"))
    )
    (net (code "228") (name "unconnected-(U$7-Pad9)") (class "Default")
      (node (ref "U$7") (pin "9") (pinfunction "9_9") (pintype "passive"))
    )
    (net (code "229") (name "unconnected-(U$7-Pad10)") (class "Default")
      (node (ref "U$7") (pin "10") (pinfunction "10_10") (pintype "passive"))
    )
    (net (code "230") (name "unconnected-(U$8-Pad1)") (class "Default")
      (node (ref "U$8") (pin "1") (pinfunction "1_1") (pintype "passive"))
    )
    (net (code "231") (name "unconnected-(U$8-Pad2)") (class "Default")
      (node (ref "U$8") (pin "2") (pinfunction "2_2") (pintype "passive"))
    )
    (net (code "232") (name "unconnected-(U$8-Pad3)") (class "Default")
      (node (ref "U$8") (pin "3") (pinfunction "3_3") (pintype "passive"))
    )
    (net (code "233") (name "unconnected-(U$8-Pad4)") (class "Default")
      (node (ref "U$8") (pin "4") (pinfunction "4_4") (pintype "passive"))
    )
    (net (code "234") (name "unconnected-(U$8-Pad5)") (class "Default")
      (node (ref "U$8") (pin "5") (pinfunction "5_5") (pintype "passive"))
    )
    (net (code "235") (name "unconnected-(U$8-Pad10)") (class "Default")
      (node (ref "U$8") (pin "10") (pinfunction "10_10") (pintype "passive"))
    )
    (net (code "236") (name "unconnected-(U$9-Pad1)") (class "Default")
      (node (ref "U$9") (pin "1") (pinfunction "1_1") (pintype "passive"))
    )
    (net (code "237") (name "unconnected-(U$9-Pad10)") (class "Default")
      (node (ref "U$9") (pin "10") (pinfunction "10_10") (pintype "passive"))
    )
    (net (code "238") (name "unconnected-(U$10-Pad1)") (class "Default")
      (node (ref "U$10") (pin "1") (pinfunction "1_1") (pintype "passive"))
    )
    (net (code "239") (name "unconnected-(U$10-Pad10)") (class "Default")
      (node (ref "U$10") (pin "10") (pinfunction "10_10") (pintype "passive"))
    )
  )
)
